# ioboard-left.net
KiCad netlist of a schematic drawn in EAGLE
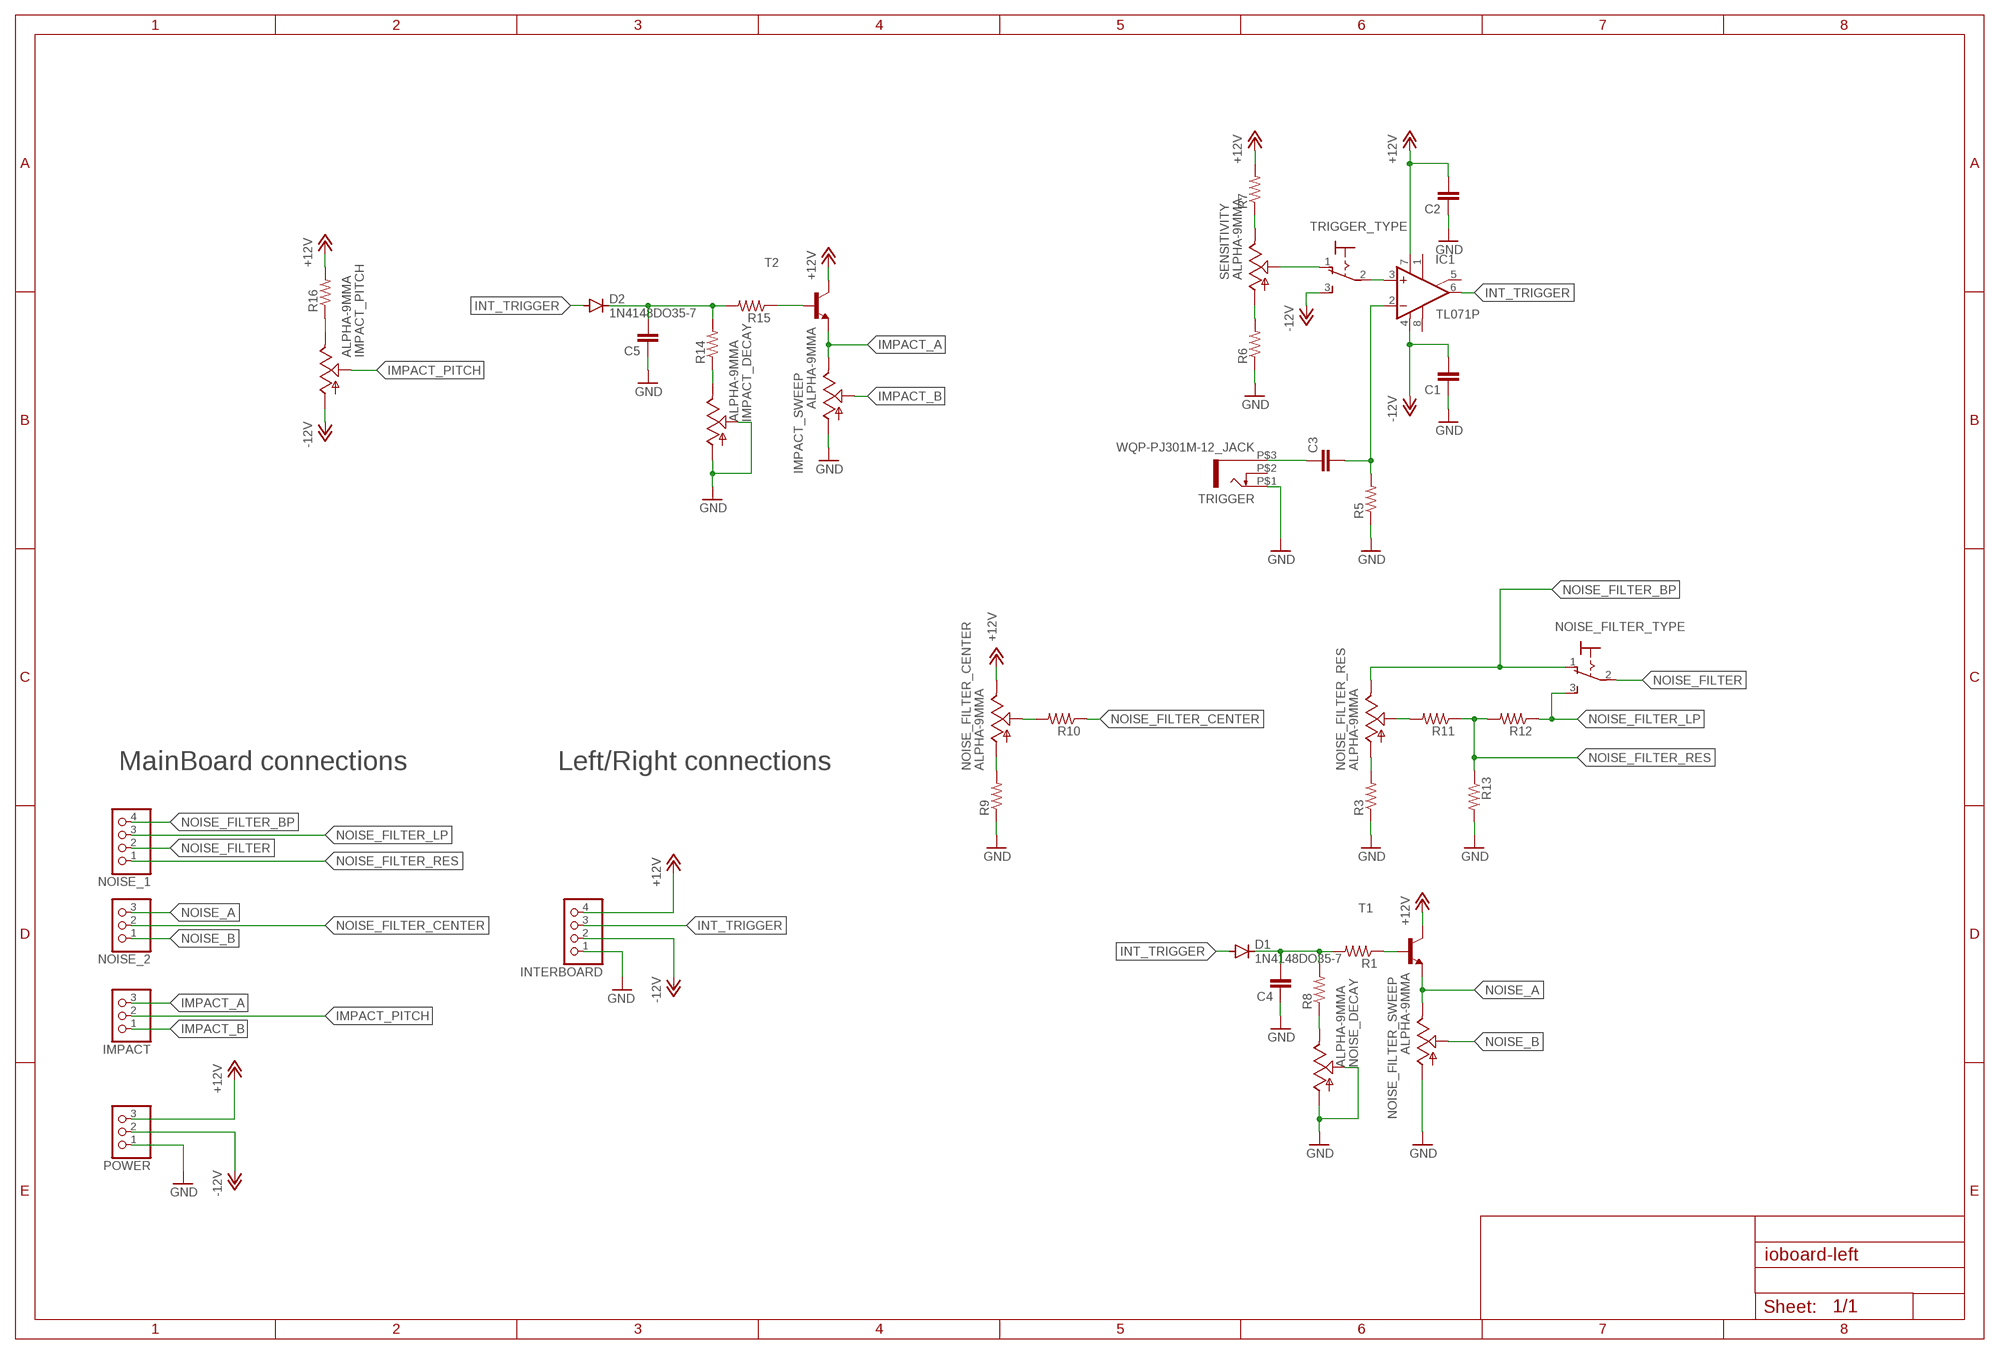
[diagram p0: schematic, sheet 1]

(export (version "E")
  (design (tool "Eeschema 10.0.6"))
  (components
    (comp (ref "C1")
      (value "C-EU050-024X044")
      (footprint "eagle-import:C050-024X044")
      (libsource (lib "eagle-import") (part "C-EU050-024X044"))
    )
    (comp (ref "C2")
      (value "C-EU050-024X044")
      (footprint "eagle-import:C050-024X044")
      (libsource (lib "eagle-import") (part "C-EU050-024X044"))
    )
    (comp (ref "C3")
      (value "C-EU050-024X044")
      (footprint "eagle-import:C050-024X044")
      (libsource (lib "eagle-import") (part "C-EU050-024X044"))
    )
    (comp (ref "C4")
      (value "C-EU050-024X044")
      (footprint "eagle-import:C050-024X044")
      (libsource (lib "eagle-import") (part "C-EU050-024X044"))
    )
    (comp (ref "C5")
      (value "C-EU050-024X044")
      (footprint "eagle-import:C050-024X044")
      (libsource (lib "eagle-import") (part "C-EU050-024X044"))
    )
    (comp (ref "D1")
      (value "1N4148DO35-7")
      (footprint "eagle-import:DO35-7")
      (libsource (lib "eagle-import") (part "1N4148DO35-7"))
    )
    (comp (ref "D2")
      (value "1N4148DO35-7")
      (footprint "eagle-import:DO35-7")
      (libsource (lib "eagle-import") (part "1N4148DO35-7"))
    )
    (comp (ref "IC1")
      (value "TL071P")
      (footprint "eagle-import:DIL08")
      (libsource (lib "eagle-import") (part "TL071P"))
    )
    (comp (ref "IMPACT")
      (value "PINHD-1X3")
      (footprint "eagle-import:1X03")
      (libsource (lib "eagle-import") (part "PINHD-1X3"))
    )
    (comp (ref "IMPACT_DECAY")
      (value "ALPHA-9MMA")
      (footprint "eagle-import:EVUF")
      (libsource (lib "eagle-import") (part "ALPHA-9MMA"))
    )
    (comp (ref "IMPACT_PITCH")
      (value "ALPHA-9MMA")
      (footprint "eagle-import:EVUF")
      (libsource (lib "eagle-import") (part "ALPHA-9MMA"))
    )
    (comp (ref "IMPACT_SWEEP")
      (value "ALPHA-9MMA")
      (footprint "eagle-import:EVUF")
      (libsource (lib "eagle-import") (part "ALPHA-9MMA"))
    )
    (comp (ref "INTERBOARD")
      (value "PINHD-1X4")
      (footprint "eagle-import:1X04")
      (libsource (lib "eagle-import") (part "PINHD-1X4"))
    )
    (comp (ref "NOISE_1")
      (value "PINHD-1X4")
      (footprint "eagle-import:1X04")
      (libsource (lib "eagle-import") (part "PINHD-1X4"))
    )
    (comp (ref "NOISE_2")
      (value "PINHD-1X3")
      (footprint "eagle-import:1X03")
      (libsource (lib "eagle-import") (part "PINHD-1X3"))
    )
    (comp (ref "NOISE_DECAY")
      (value "ALPHA-9MMA")
      (footprint "eagle-import:EVUF")
      (libsource (lib "eagle-import") (part "ALPHA-9MMA"))
    )
    (comp (ref "NOISE_FILTER_CENTER")
      (value "ALPHA-9MMA")
      (footprint "eagle-import:EVUF")
      (libsource (lib "eagle-import") (part "ALPHA-9MMA"))
    )
    (comp (ref "NOISE_FILTER_RES")
      (value "ALPHA-9MMA")
      (footprint "eagle-import:EVUF")
      (libsource (lib "eagle-import") (part "ALPHA-9MMA"))
    )
    (comp (ref "NOISE_FILTER_SWEEP")
      (value "ALPHA-9MMA")
      (footprint "eagle-import:EVUF")
      (libsource (lib "eagle-import") (part "ALPHA-9MMA"))
    )
    (comp (ref "NOISE_FILTER_TYPE")
      (value "M9040P")
      (footprint "eagle-import:M9040P")
      (libsource (lib "eagle-import") (part "M9040P"))
    )
    (comp (ref "POWER")
      (value "PINHD-1X3")
      (footprint "eagle-import:1X03")
      (libsource (lib "eagle-import") (part "PINHD-1X3"))
    )
    (comp (ref "R1")
      (value "R-US_0207/7")
      (footprint "eagle-import:0207_7")
      (libsource (lib "eagle-import") (part "R-US_0207/7"))
    )
    (comp (ref "R3")
      (value "R-US_0207/7")
      (footprint "eagle-import:0207_7")
      (libsource (lib "eagle-import") (part "R-US_0207/7"))
    )
    (comp (ref "R5")
      (value "R-US_0207/7")
      (footprint "eagle-import:0207_7")
      (libsource (lib "eagle-import") (part "R-US_0207/7"))
    )
    (comp (ref "R6")
      (value "R-US_0207/7")
      (footprint "eagle-import:0207_7")
      (libsource (lib "eagle-import") (part "R-US_0207/7"))
    )
    (comp (ref "R7")
      (value "R-US_0207/7")
      (footprint "eagle-import:0207_7")
      (libsource (lib "eagle-import") (part "R-US_0207/7"))
    )
    (comp (ref "R8")
      (value "R-US_0207/7")
      (footprint "eagle-import:0207_7")
      (libsource (lib "eagle-import") (part "R-US_0207/7"))
    )
    (comp (ref "R9")
      (value "R-US_0207/7")
      (footprint "eagle-import:0207_7")
      (libsource (lib "eagle-import") (part "R-US_0207/7"))
    )
    (comp (ref "R10")
      (value "R-US_0207/7")
      (footprint "eagle-import:0207_7")
      (libsource (lib "eagle-import") (part "R-US_0207/7"))
    )
    (comp (ref "R11")
      (value "R-US_0207/7")
      (footprint "eagle-import:0207_7")
      (libsource (lib "eagle-import") (part "R-US_0207/7"))
    )
    (comp (ref "R12")
      (value "R-US_0207/7")
      (footprint "eagle-import:0207_7")
      (libsource (lib "eagle-import") (part "R-US_0207/7"))
    )
    (comp (ref "R13")
      (value "R-US_0207/7")
      (footprint "eagle-import:0207_7")
      (libsource (lib "eagle-import") (part "R-US_0207/7"))
    )
    (comp (ref "R14")
      (value "R-US_0207/7")
      (footprint "eagle-import:0207_7")
      (libsource (lib "eagle-import") (part "R-US_0207/7"))
    )
    (comp (ref "R15")
      (value "R-US_0207/7")
      (footprint "eagle-import:0207_7")
      (libsource (lib "eagle-import") (part "R-US_0207/7"))
    )
    (comp (ref "R16")
      (value "R-US_0207/7")
      (footprint "eagle-import:0207_7")
      (libsource (lib "eagle-import") (part "R-US_0207/7"))
    )
    (comp (ref "SENSITIVITY")
      (value "ALPHA-9MMA")
      (footprint "eagle-import:EVUF")
      (libsource (lib "eagle-import") (part "ALPHA-9MMA"))
    )
    (comp (ref "T1")
      (value "2N3904-NPN-TO92-EBC")
      (footprint "eagle-import:TO92-EBC")
      (libsource (lib "eagle-import") (part "-NPN-TO92-EBC2N3904"))
    )
    (comp (ref "T2")
      (value "2N3904-NPN-TO92-EBC")
      (footprint "eagle-import:TO92-EBC")
      (libsource (lib "eagle-import") (part "-NPN-TO92-EBC2N3904"))
    )
    (comp (ref "TRIGGER")
      (value "WQP-PJ301M-12_JACK")
      (footprint "eagle-import:WQP-PJ301M-12_JACK")
      (libsource (lib "eagle-import") (part "WQP-PJ301M-12_JACK"))
    )
    (comp (ref "TRIGGER_TYPE")
      (value "M9040P")
      (footprint "eagle-import:M9040P")
      (libsource (lib "eagle-import") (part "M9040P"))
    )
  )
  (nets
    (net (code "1") (name "+12V") (class "Default")
      (node (ref "C2") (pin "2") (pinfunction "2_2") (pintype "passive"))
      (node (ref "IC1") (pin "7") (pinfunction "V+_7") (pintype "power_in"))
      (node (ref "INTERBOARD") (pin "4") (pinfunction "4_4") (pintype "passive"))
      (node (ref "NOISE_FILTER_CENTER") (pin "3") (pinfunction "E_3") (pintype "passive"))
      (node (ref "POWER") (pin "3") (pinfunction "3_3") (pintype "passive"))
      (node (ref "R16") (pin "2") (pinfunction "2_2") (pintype "passive"))
      (node (ref "R7") (pin "2") (pinfunction "2_2") (pintype "passive"))
      (node (ref "T1") (pin "C") (pinfunction "C_C") (pintype "passive"))
      (node (ref "T2") (pin "C") (pinfunction "C_C") (pintype "passive"))
    )
    (net (code "2") (name "-12V") (class "Default")
      (node (ref "C1") (pin "2") (pinfunction "2_2") (pintype "passive"))
      (node (ref "IC1") (pin "4") (pinfunction "V-_4") (pintype "power_in"))
      (node (ref "IMPACT_PITCH") (pin "1") (pinfunction "A_1") (pintype "passive"))
      (node (ref "INTERBOARD") (pin "2") (pinfunction "2_2") (pintype "passive"))
      (node (ref "POWER") (pin "2") (pinfunction "2_2") (pintype "passive"))
      (node (ref "TRIGGER_TYPE") (pin "3") (pinfunction "S_3") (pintype "passive"))
    )
    (net (code "3") (name "GND") (class "Default")
      (node (ref "C1") (pin "1") (pinfunction "1_1") (pintype "passive"))
      (node (ref "C2") (pin "1") (pinfunction "1_1") (pintype "passive"))
      (node (ref "C4") (pin "1") (pinfunction "1_1") (pintype "passive"))
      (node (ref "C5") (pin "1") (pinfunction "1_1") (pintype "passive"))
      (node (ref "IMPACT_DECAY") (pin "1") (pinfunction "A_1") (pintype "passive"))
      (node (ref "IMPACT_DECAY") (pin "2") (pinfunction "S_2") (pintype "passive"))
      (node (ref "IMPACT_SWEEP") (pin "1") (pinfunction "A_1") (pintype "passive"))
      (node (ref "INTERBOARD") (pin "1") (pinfunction "1_1") (pintype "passive"))
      (node (ref "NOISE_DECAY") (pin "1") (pinfunction "A_1") (pintype "passive"))
      (node (ref "NOISE_DECAY") (pin "2") (pinfunction "S_2") (pintype "passive"))
      (node (ref "NOISE_FILTER_SWEEP") (pin "1") (pinfunction "A_1") (pintype "passive"))
      (node (ref "POWER") (pin "1") (pinfunction "1_1") (pintype "passive"))
      (node (ref "R13") (pin "2") (pinfunction "2_2") (pintype "passive"))
      (node (ref "R3") (pin "1") (pinfunction "1_1") (pintype "passive"))
      (node (ref "R5") (pin "1") (pinfunction "1_1") (pintype "passive"))
      (node (ref "R6") (pin "1") (pinfunction "1_1") (pintype "passive"))
      (node (ref "R9") (pin "1") (pinfunction "1_1") (pintype "passive"))
      (node (ref "TRIGGER") (pin "P$1") (pinfunction "2_P$1") (pintype "passive"))
    )
    (net (code "4") (name "IMPACT_A") (class "Default")
      (node (ref "IMPACT") (pin "3") (pinfunction "3_3") (pintype "passive"))
      (node (ref "IMPACT_SWEEP") (pin "3") (pinfunction "E_3") (pintype "passive"))
      (node (ref "T2") (pin "E") (pinfunction "E_E") (pintype "passive"))
    )
    (net (code "5") (name "IMPACT_B") (class "Default")
      (node (ref "IMPACT") (pin "1") (pinfunction "1_1") (pintype "passive"))
      (node (ref "IMPACT_SWEEP") (pin "2") (pinfunction "S_2") (pintype "passive"))
    )
    (net (code "6") (name "IMPACT_PITCH") (class "Default")
      (node (ref "IMPACT") (pin "2") (pinfunction "2_2") (pintype "passive"))
      (node (ref "IMPACT_PITCH") (pin "2") (pinfunction "S_2") (pintype "passive"))
    )
    (net (code "7") (name "INT_TRIGGER") (class "Default")
      (node (ref "D1") (pin "A") (pinfunction "A_A") (pintype "passive"))
      (node (ref "D2") (pin "A") (pinfunction "A_A") (pintype "passive"))
      (node (ref "IC1") (pin "6") (pinfunction "OUT_6") (pintype "output"))
      (node (ref "INTERBOARD") (pin "3") (pinfunction "3_3") (pintype "passive"))
    )
    (net (code "8") (name "NOISE_A") (class "Default")
      (node (ref "NOISE_2") (pin "3") (pinfunction "3_3") (pintype "passive"))
      (node (ref "NOISE_FILTER_SWEEP") (pin "3") (pinfunction "E_3") (pintype "passive"))
      (node (ref "T1") (pin "E") (pinfunction "E_E") (pintype "passive"))
    )
    (net (code "9") (name "NOISE_B") (class "Default")
      (node (ref "NOISE_2") (pin "1") (pinfunction "1_1") (pintype "passive"))
      (node (ref "NOISE_FILTER_SWEEP") (pin "2") (pinfunction "S_2") (pintype "passive"))
    )
    (net (code "10") (name "NOISE_FILTER") (class "Default")
      (node (ref "NOISE_1") (pin "2") (pinfunction "2_2") (pintype "passive"))
      (node (ref "NOISE_FILTER_TYPE") (pin "2") (pinfunction "P_2") (pintype "passive"))
    )
    (net (code "11") (name "NOISE_FILTER_BP") (class "Default")
      (node (ref "NOISE_1") (pin "4") (pinfunction "4_4") (pintype "passive"))
      (node (ref "NOISE_FILTER_RES") (pin "3") (pinfunction "E_3") (pintype "passive"))
      (node (ref "NOISE_FILTER_TYPE") (pin "1") (pinfunction "O_1") (pintype "passive"))
    )
    (net (code "12") (name "NOISE_FILTER_CENTER") (class "Default")
      (node (ref "NOISE_2") (pin "2") (pinfunction "2_2") (pintype "passive"))
      (node (ref "R10") (pin "1") (pinfunction "1_1") (pintype "passive"))
    )
    (net (code "13") (name "NOISE_FILTER_LP") (class "Default")
      (node (ref "NOISE_1") (pin "3") (pinfunction "3_3") (pintype "passive"))
      (node (ref "NOISE_FILTER_TYPE") (pin "3") (pinfunction "S_3") (pintype "passive"))
      (node (ref "R12") (pin "1") (pinfunction "1_1") (pintype "passive"))
    )
    (net (code "14") (name "NOISE_FILTER_RES") (class "Default")
      (node (ref "NOISE_1") (pin "1") (pinfunction "1_1") (pintype "passive"))
      (node (ref "R11") (pin "1") (pinfunction "1_1") (pintype "passive"))
      (node (ref "R12") (pin "2") (pinfunction "2_2") (pintype "passive"))
      (node (ref "R13") (pin "1") (pinfunction "1_1") (pintype "passive"))
    )
    (net (code "15") (name "Net-(C4-Pad2)") (class "Default")
      (node (ref "C4") (pin "2") (pinfunction "2_2") (pintype "passive"))
      (node (ref "D1") (pin "C") (pinfunction "C_C") (pintype "passive"))
      (node (ref "R1") (pin "2") (pinfunction "2_2") (pintype "passive"))
      (node (ref "R8") (pin "2") (pinfunction "2_2") (pintype "passive"))
    )
    (net (code "16") (name "Net-(C5-Pad2)") (class "Default")
      (node (ref "C5") (pin "2") (pinfunction "2_2") (pintype "passive"))
      (node (ref "D2") (pin "C") (pinfunction "C_C") (pintype "passive"))
      (node (ref "R14") (pin "2") (pinfunction "2_2") (pintype "passive"))
      (node (ref "R15") (pin "2") (pinfunction "2_2") (pintype "passive"))
    )
    (net (code "17") (name "Net-(IC1-+IN)") (class "Default")
      (node (ref "IC1") (pin "3") (pinfunction "+IN_3") (pintype "input"))
      (node (ref "TRIGGER_TYPE") (pin "2") (pinfunction "P_2") (pintype "passive"))
    )
    (net (code "18") (name "Net-(IC1--IN)") (class "Default")
      (node (ref "C3") (pin "2") (pinfunction "2_2") (pintype "passive"))
      (node (ref "IC1") (pin "2") (pinfunction "-IN_2") (pintype "input"))
      (node (ref "R5") (pin "2") (pinfunction "2_2") (pintype "passive"))
    )
    (net (code "19") (name "Net-(IMPACT_DECAY-E)") (class "Default")
      (node (ref "IMPACT_DECAY") (pin "3") (pinfunction "E_3") (pintype "passive"))
      (node (ref "R14") (pin "1") (pinfunction "1_1") (pintype "passive"))
    )
    (net (code "20") (name "Net-(IMPACT_PITCH-E)") (class "Default")
      (node (ref "IMPACT_PITCH") (pin "3") (pinfunction "E_3") (pintype "passive"))
      (node (ref "R16") (pin "1") (pinfunction "1_1") (pintype "passive"))
    )
    (net (code "21") (name "Net-(NOISE_DECAY-E)") (class "Default")
      (node (ref "NOISE_DECAY") (pin "3") (pinfunction "E_3") (pintype "passive"))
      (node (ref "R8") (pin "1") (pinfunction "1_1") (pintype "passive"))
    )
    (net (code "22") (name "Net-(NOISE_FILTER_CENTER-A)") (class "Default")
      (node (ref "NOISE_FILTER_CENTER") (pin "1") (pinfunction "A_1") (pintype "passive"))
      (node (ref "R9") (pin "2") (pinfunction "2_2") (pintype "passive"))
    )
    (net (code "23") (name "Net-(NOISE_FILTER_CENTER-S)") (class "Default")
      (node (ref "NOISE_FILTER_CENTER") (pin "2") (pinfunction "S_2") (pintype "passive"))
      (node (ref "R10") (pin "2") (pinfunction "2_2") (pintype "passive"))
    )
    (net (code "24") (name "Net-(NOISE_FILTER_RES-A)") (class "Default")
      (node (ref "NOISE_FILTER_RES") (pin "1") (pinfunction "A_1") (pintype "passive"))
      (node (ref "R3") (pin "2") (pinfunction "2_2") (pintype "passive"))
    )
    (net (code "25") (name "Net-(NOISE_FILTER_RES-S)") (class "Default")
      (node (ref "NOISE_FILTER_RES") (pin "2") (pinfunction "S_2") (pintype "passive"))
      (node (ref "R11") (pin "2") (pinfunction "2_2") (pintype "passive"))
    )
    (net (code "26") (name "Net-(R1-Pad1)") (class "Default")
      (node (ref "R1") (pin "1") (pinfunction "1_1") (pintype "passive"))
      (node (ref "T1") (pin "B") (pinfunction "B_B") (pintype "passive"))
    )
    (net (code "27") (name "Net-(R15-Pad1)") (class "Default")
      (node (ref "R15") (pin "1") (pinfunction "1_1") (pintype "passive"))
      (node (ref "T2") (pin "B") (pinfunction "B_B") (pintype "passive"))
    )
    (net (code "28") (name "Net-(SENSITIVITY-A)") (class "Default")
      (node (ref "R6") (pin "2") (pinfunction "2_2") (pintype "passive"))
      (node (ref "SENSITIVITY") (pin "1") (pinfunction "A_1") (pintype "passive"))
    )
    (net (code "29") (name "Net-(SENSITIVITY-E)") (class "Default")
      (node (ref "R7") (pin "1") (pinfunction "1_1") (pintype "passive"))
      (node (ref "SENSITIVITY") (pin "3") (pinfunction "E_3") (pintype "passive"))
    )
    (net (code "30") (name "Net-(SENSITIVITY-S)") (class "Default")
      (node (ref "SENSITIVITY") (pin "2") (pinfunction "S_2") (pintype "passive"))
      (node (ref "TRIGGER_TYPE") (pin "1") (pinfunction "O_1") (pintype "passive"))
    )
    (net (code "31") (name "Net-(TRIGGER-1)") (class "Default")
      (node (ref "C3") (pin "1") (pinfunction "1_1") (pintype "passive"))
      (node (ref "TRIGGER") (pin "P$3") (pinfunction "1_P$3") (pintype "passive"))
    )
    (net (code "32") (name "unconnected-(IC1-ON1-Pad1)") (class "Default")
      (node (ref "IC1") (pin "1") (pinfunction "ON1_1") (pintype "passive"))
    )
    (net (code "33") (name "unconnected-(IC1-ON2-Pad5)") (class "Default")
      (node (ref "IC1") (pin "5") (pinfunction "ON2_5") (pintype "passive"))
    )
    (net (code "34") (name "unconnected-(IC1-OPT-Pad8)") (class "Default")
      (node (ref "IC1") (pin "8") (pinfunction "OPT_8") (pintype "passive"))
    )
    (net (code "35") (name "unconnected-(TRIGGER-3-PadP$2)") (class "Default")
      (node (ref "TRIGGER") (pin "P$2") (pinfunction "3_P$2") (pintype "passive"))
    )
  )
)
